# VGA-Slot14.net
KiCad netlist of a schematic drawn in EAGLE
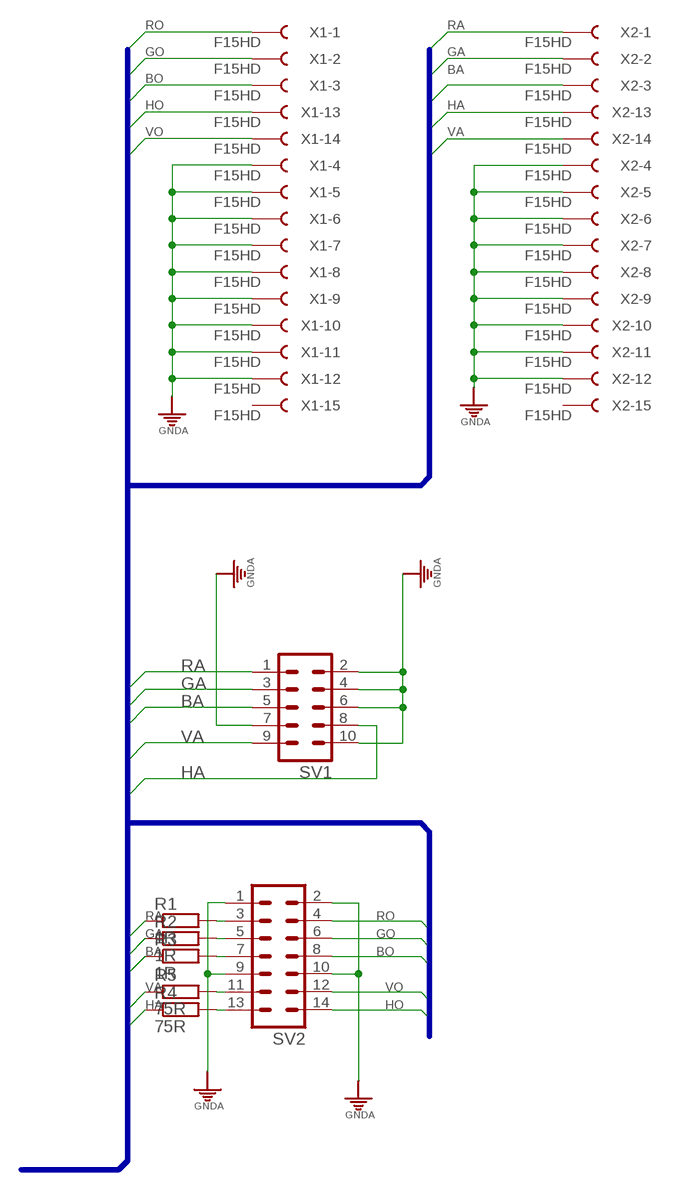
[diagram p0: schematic, sheet 1]

(export (version "E")
  (design (tool "Eeschema 10.0.6"))
  (components
    (comp (ref "R1")
      (value "1R")
      (footprint "eagle-import:R0805")
      (libsource (lib "eagle-import") (part "R-EU_R0805"))
    )
    (comp (ref "R2")
      (value "1R")
      (footprint "eagle-import:R0805")
      (libsource (lib "eagle-import") (part "R-EU_R0805"))
    )
    (comp (ref "R3")
      (value "1R")
      (footprint "eagle-import:R0805")
      (libsource (lib "eagle-import") (part "R-EU_R0805"))
    )
    (comp (ref "R4")
      (value "75R")
      (footprint "eagle-import:R0805")
      (libsource (lib "eagle-import") (part "R-EU_R0805"))
    )
    (comp (ref "R5")
      (value "75R")
      (footprint "eagle-import:R0805")
      (libsource (lib "eagle-import") (part "R-EU_R0805"))
    )
    (comp (ref "SV1")
      (value "ML10")
      (footprint "eagle-import:ML10")
      (libsource (lib "eagle-import") (part "ML10"))
    )
    (comp (ref "SV2")
      (value "ML14")
      (footprint "eagle-import:ML14")
      (libsource (lib "eagle-import") (part "ML14"))
    )
    (comp (ref "X1")
      (value "F15HD")
      (footprint "eagle-import:F15HD")
      (libsource (lib "eagle-import") (part "F15HD"))
    )
    (comp (ref "X2")
      (value "F15HD")
      (footprint "eagle-import:F15HD")
      (libsource (lib "eagle-import") (part "F15HD"))
    )
  )
  (nets
    (net (code "1") (name "/BA") (class "Default")
      (node (ref "R3") (pin "1") (pinfunction "1_1") (pintype "passive"))
      (node (ref "SV1") (pin "5") (pinfunction "5_5") (pintype "passive"))
      (node (ref "X2") (pin "3") (pinfunction "F_3") (pintype "passive"))
    )
    (net (code "2") (name "/BO") (class "Default")
      (node (ref "SV2") (pin "8") (pinfunction "8_8") (pintype "passive"))
      (node (ref "X1") (pin "3") (pinfunction "F_3") (pintype "passive"))
    )
    (net (code "3") (name "/GA") (class "Default")
      (node (ref "R2") (pin "1") (pinfunction "1_1") (pintype "passive"))
      (node (ref "SV1") (pin "3") (pinfunction "3_3") (pintype "passive"))
      (node (ref "X2") (pin "2") (pinfunction "F_2") (pintype "passive"))
    )
    (net (code "4") (name "/GO") (class "Default")
      (node (ref "SV2") (pin "6") (pinfunction "6_6") (pintype "passive"))
      (node (ref "X1") (pin "2") (pinfunction "F_2") (pintype "passive"))
    )
    (net (code "5") (name "/HA") (class "Default")
      (node (ref "R4") (pin "1") (pinfunction "1_1") (pintype "passive"))
      (node (ref "SV1") (pin "8") (pinfunction "8_8") (pintype "passive"))
      (node (ref "X2") (pin "13") (pinfunction "F_13") (pintype "passive"))
    )
    (net (code "6") (name "/HO") (class "Default")
      (node (ref "SV2") (pin "14") (pinfunction "14_14") (pintype "passive"))
      (node (ref "X1") (pin "13") (pinfunction "F_13") (pintype "passive"))
    )
    (net (code "7") (name "/RA") (class "Default")
      (node (ref "R1") (pin "1") (pinfunction "1_1") (pintype "passive"))
      (node (ref "SV1") (pin "1") (pinfunction "1_1") (pintype "passive"))
      (node (ref "X2") (pin "1") (pinfunction "F_1") (pintype "passive"))
    )
    (net (code "8") (name "/RO") (class "Default")
      (node (ref "SV2") (pin "4") (pinfunction "4_4") (pintype "passive"))
      (node (ref "X1") (pin "1") (pinfunction "F_1") (pintype "passive"))
    )
    (net (code "9") (name "/VA") (class "Default")
      (node (ref "R5") (pin "1") (pinfunction "1_1") (pintype "passive"))
      (node (ref "SV1") (pin "9") (pinfunction "9_9") (pintype "passive"))
      (node (ref "X2") (pin "14") (pinfunction "F_14") (pintype "passive"))
    )
    (net (code "10") (name "/VO") (class "Default")
      (node (ref "SV2") (pin "12") (pinfunction "12_12") (pintype "passive"))
      (node (ref "X1") (pin "14") (pinfunction "F_14") (pintype "passive"))
    )
    (net (code "12") (name "GNDA") (class "Default")
      (node (ref "SV1") (pin "10") (pinfunction "10_10") (pintype "passive"))
      (node (ref "SV1") (pin "2") (pinfunction "2_2") (pintype "passive"))
      (node (ref "SV1") (pin "4") (pinfunction "4_4") (pintype "passive"))
      (node (ref "SV1") (pin "6") (pinfunction "6_6") (pintype "passive"))
      (node (ref "SV1") (pin "7") (pinfunction "7_7") (pintype "passive"))
      (node (ref "SV2") (pin "1") (pinfunction "1_1") (pintype "passive"))
      (node (ref "SV2") (pin "10") (pinfunction "10_10") (pintype "passive"))
      (node (ref "SV2") (pin "2") (pinfunction "2_2") (pintype "passive"))
      (node (ref "SV2") (pin "9") (pinfunction "9_9") (pintype "passive"))
      (node (ref "X1") (pin "10") (pinfunction "F_10") (pintype "passive"))
      (node (ref "X1") (pin "11") (pinfunction "F_11") (pintype "passive"))
      (node (ref "X1") (pin "12") (pinfunction "F_12") (pintype "passive"))
      (node (ref "X1") (pin "4") (pinfunction "F_4") (pintype "passive"))
      (node (ref "X1") (pin "5") (pinfunction "F_5") (pintype "passive"))
      (node (ref "X1") (pin "6") (pinfunction "F_6") (pintype "passive"))
      (node (ref "X1") (pin "7") (pinfunction "F_7") (pintype "passive"))
      (node (ref "X1") (pin "8") (pinfunction "F_8") (pintype "passive"))
      (node (ref "X1") (pin "9") (pinfunction "F_9") (pintype "passive"))
      (node (ref "X2") (pin "10") (pinfunction "F_10") (pintype "passive"))
      (node (ref "X2") (pin "11") (pinfunction "F_11") (pintype "passive"))
      (node (ref "X2") (pin "12") (pinfunction "F_12") (pintype "passive"))
      (node (ref "X2") (pin "4") (pinfunction "F_4") (pintype "passive"))
      (node (ref "X2") (pin "5") (pinfunction "F_5") (pintype "passive"))
      (node (ref "X2") (pin "6") (pinfunction "F_6") (pintype "passive"))
      (node (ref "X2") (pin "7") (pinfunction "F_7") (pintype "passive"))
      (node (ref "X2") (pin "8") (pinfunction "F_8") (pintype "passive"))
      (node (ref "X2") (pin "9") (pinfunction "F_9") (pintype "passive"))
    )
    (net (code "13") (name "Net-(R1-Pad2)") (class "Default")
      (node (ref "R1") (pin "2") (pinfunction "2_2") (pintype "passive"))
      (node (ref "SV2") (pin "3") (pinfunction "3_3") (pintype "passive"))
    )
    (net (code "14") (name "Net-(R2-Pad2)") (class "Default")
      (node (ref "R2") (pin "2") (pinfunction "2_2") (pintype "passive"))
      (node (ref "SV2") (pin "5") (pinfunction "5_5") (pintype "passive"))
    )
    (net (code "15") (name "Net-(R3-Pad2)") (class "Default")
      (node (ref "R3") (pin "2") (pinfunction "2_2") (pintype "passive"))
      (node (ref "SV2") (pin "7") (pinfunction "7_7") (pintype "passive"))
    )
    (net (code "16") (name "Net-(R4-Pad2)") (class "Default")
      (node (ref "R4") (pin "2") (pinfunction "2_2") (pintype "passive"))
      (node (ref "SV2") (pin "13") (pinfunction "13_13") (pintype "passive"))
    )
    (net (code "17") (name "Net-(R5-Pad2)") (class "Default")
      (node (ref "R5") (pin "2") (pinfunction "2_2") (pintype "passive"))
      (node (ref "SV2") (pin "11") (pinfunction "11_11") (pintype "passive"))
    )
    (net (code "18") (name "unconnected-(X1G-F-Pad15)") (class "Default")
      (node (ref "X1") (pin "15") (pinfunction "F_15") (pintype "passive"))
    )
    (net (code "19") (name "unconnected-(X2G-F-Pad15)") (class "Default")
      (node (ref "X2") (pin "15") (pinfunction "F_15") (pintype "passive"))
    )
  )
)
